# Sheet1.net
KiCad netlist of a schematic drawn in Altium Designer
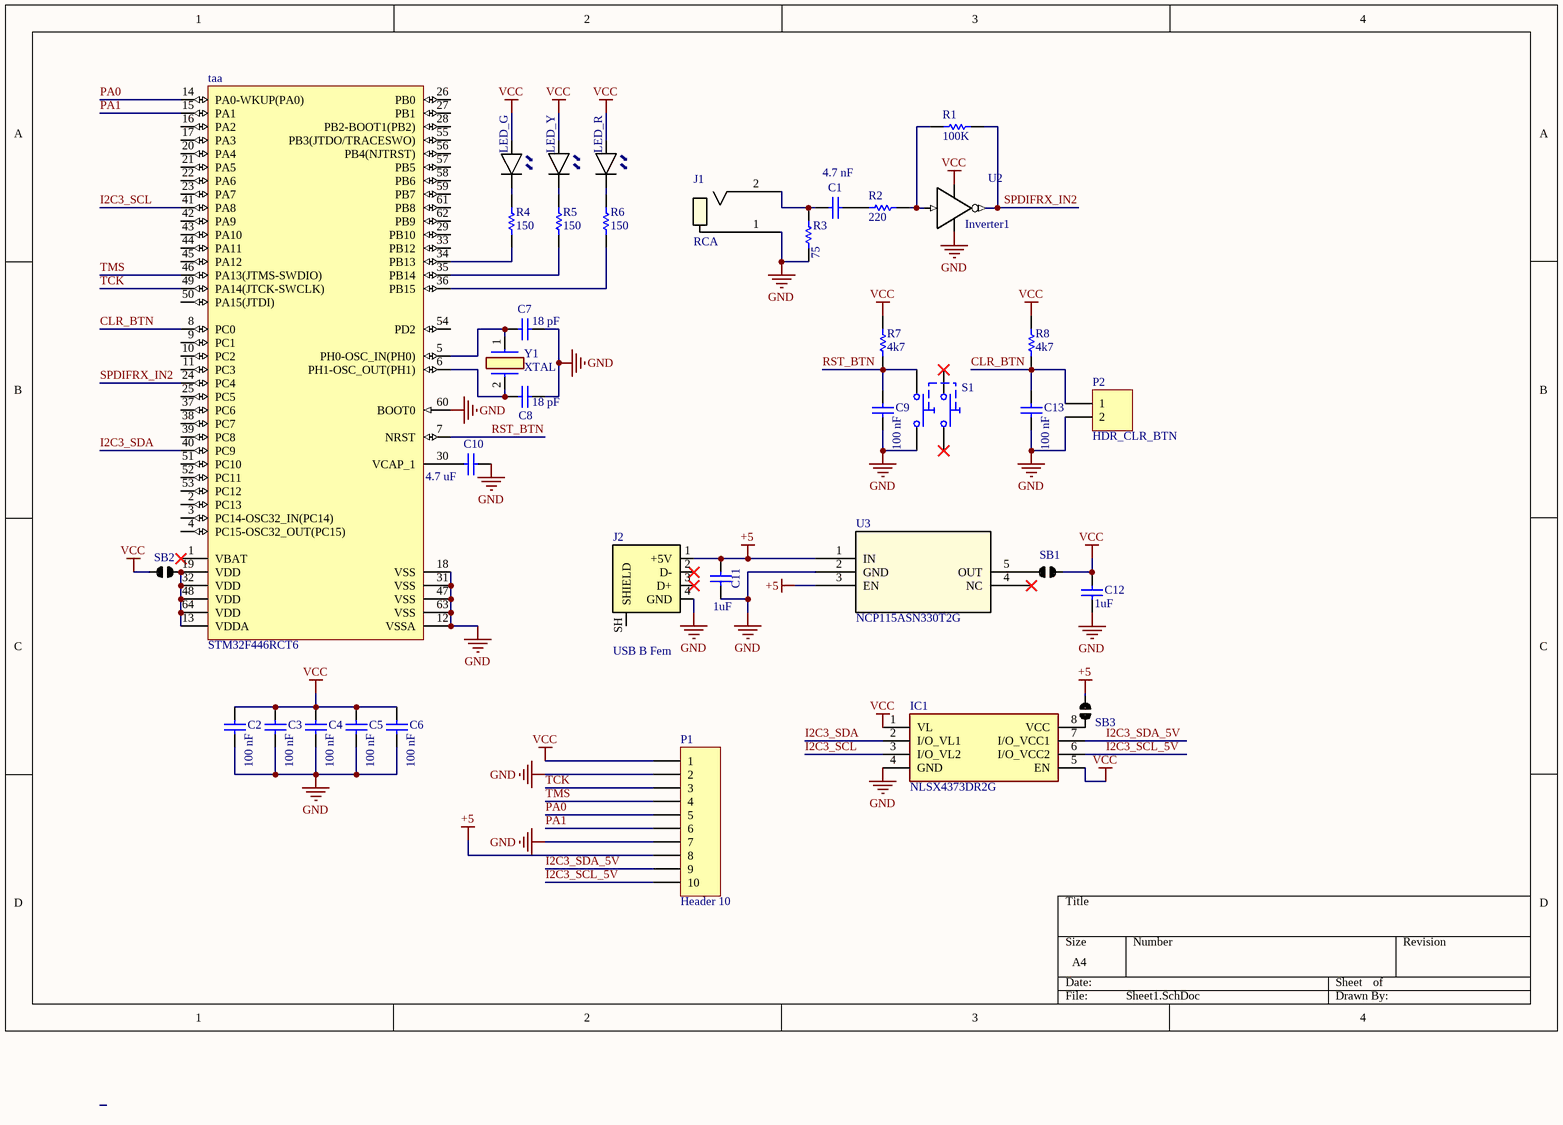
[diagram p0: Sheet1.SchDoc]

(export (version "E")
  (design (tool "Eeschema 10.0.6"))
  (components
    (comp (ref "C1")
      (value "4.7 nF")
      (footprint "RESC3216X70N")
      (description "Capacitor")
      (fields (field (name "Comment") "Cap") (field (name "PUBLISHER") "Altium Limited"))
      (libsource (lib "Miscellaneous Devices") (part "Cap"))
    )
    (comp (ref "C2")
      (value "100 nF")
      (footprint "RESC3216X70N")
      (description "Capacitor")
      (fields (field (name "Comment") "Cap") (field (name "PUBLISHER") "Altium Limited"))
      (libsource (lib "Miscellaneous Devices") (part "Cap"))
    )
    (comp (ref "C3")
      (value "100 nF")
      (footprint "RESC3216X70N")
      (description "Capacitor")
      (fields (field (name "Comment") "Cap") (field (name "PUBLISHER") "Altium Limited"))
      (libsource (lib "Miscellaneous Devices") (part "Cap"))
    )
    (comp (ref "C4")
      (value "100 nF")
      (footprint "RESC3216X70N")
      (description "Capacitor")
      (fields (field (name "Comment") "Cap") (field (name "PUBLISHER") "Altium Limited"))
      (libsource (lib "Miscellaneous Devices") (part "Cap"))
    )
    (comp (ref "C5")
      (value "100 nF")
      (footprint "RESC3216X70N")
      (description "Capacitor")
      (fields (field (name "Comment") "Cap") (field (name "PUBLISHER") "Altium Limited"))
      (libsource (lib "Miscellaneous Devices") (part "Cap"))
    )
    (comp (ref "C6")
      (value "100 nF")
      (footprint "RESC3216X70N")
      (description "Capacitor")
      (fields (field (name "Comment") "Cap") (field (name "PUBLISHER") "Altium Limited"))
      (libsource (lib "Miscellaneous Devices") (part "Cap"))
    )
    (comp (ref "C7")
      (value "18 pF")
      (footprint "RESC3216X70N")
      (description "Capacitor")
      (fields (field (name "Comment") "Cap") (field (name "PUBLISHER") "Altium Limited"))
      (libsource (lib "Miscellaneous Devices") (part "Cap"))
    )
    (comp (ref "C8")
      (value "18 pF")
      (footprint "RESC3216X70N")
      (description "Capacitor")
      (fields (field (name "Comment") "Cap") (field (name "PUBLISHER") "Altium Limited"))
      (libsource (lib "Miscellaneous Devices") (part "Cap"))
    )
    (comp (ref "C9")
      (value "100 nF")
      (footprint "RESC3216X70N")
      (description "Capacitor")
      (fields (field (name "Comment") "Cap") (field (name "PUBLISHER") "Altium Limited"))
      (libsource (lib "Miscellaneous Devices") (part "Cap"))
    )
    (comp (ref "C10")
      (value "4.7 uF")
      (footprint "CAPPRD250W50D655H1250")
      (description "Capacitor")
      (fields (field (name "Comment") "Cap") (field (name "PUBLISHER") "Altium Limited"))
      (libsource (lib "Miscellaneous Devices") (part "Cap"))
    )
    (comp (ref "C11")
      (value "1uF")
      (footprint "CAPPRD250W50D655H1250")
      (description "Capacitor")
      (fields (field (name "Comment") "Cap") (field (name "PUBLISHER") "Altium Limited"))
      (libsource (lib "Miscellaneous Devices") (part "Cap"))
    )
    (comp (ref "C12")
      (value "1uF")
      (footprint "CAPPRD250W50D655H1250")
      (description "Capacitor")
      (fields (field (name "Comment") "Cap") (field (name "PUBLISHER") "Altium Limited"))
      (libsource (lib "Miscellaneous Devices") (part "Cap"))
    )
    (comp (ref "C13")
      (value "100 nF")
      (footprint "RESC3216X70N")
      (description "Capacitor")
      (fields (field (name "Comment") "Cap") (field (name "PUBLISHER") "Altium Limited"))
      (libsource (lib "Miscellaneous Devices") (part "Cap"))
    )
    (comp (ref "IC1")
      (value "NLSX4373DR2G")
      (footprint "SamacSys:SOIC127P600X175-8N")
      (description "Integrated Circuit")
      (fields (field (name "MOUSER PART NUMBER") "863-NLSX4373DR2G"))
      (libsource (lib "*") (part "NLSX4373DR2G"))
    )
    (comp (ref "J1")
      (value "RCA")
      (footprint "KLPX-0848A-2-B_KYC")
      (description "No Description Available")
      (fields
        (field (name "MANUFACTURER_PART_NUMBER") "KLPX-0848A-2-B")
        (field (name "COPYRIGHT") "Copyright (C) 2023 Ultra Librarian. All rights reserved.")
      )
      (libsource (lib "KLPX-0848A-2-B") (part "KLPX-0848A-2-B"))
    )
    (comp (ref "J2") (value "USB B Fem") (footprint "UJ2BH1TH") (libsource (lib "USB") (part "USB B Fem")))
    (comp (ref "LED_G")
      (value "fucking led maat hoe moeilijk ist kutprogram")
      (footprint "LED_SSL-LX4673GD-LA20")
      (libsource (lib "Schlib1") (part "fucking led maat hoe moeilijk ist kutprogram"))
    )
    (comp (ref "LED_R")
      (value "fucking led maat hoe moeilijk ist kutprogram")
      (footprint "LED_SSL-LX4673GD-LA20")
      (libsource (lib "Schlib1") (part "fucking led maat hoe moeilijk ist kutprogram"))
    )
    (comp (ref "LED_Y")
      (value "fucking led maat hoe moeilijk ist kutprogram")
      (footprint "LED_SSL-LX4673GD-LA20")
      (libsource (lib "Schlib1") (part "fucking led maat hoe moeilijk ist kutprogram"))
    )
    (comp (ref "P1")
      (value "Header 10")
      (footprint "HDR1X10")
      (description "Header, 10-Pin")
      (fields (field (name "PUBLISHER") "Altium Limited"))
      (libsource (lib "Miscellaneous Connectors") (part "Header 10"))
    )
    (comp (ref "P2")
      (value "HDR_CLR_BTN")
      (footprint "HDR1X2")
      (description "Header, 2-Pin")
      (fields (field (name "PUBLISHER") "Altium Limited"))
      (libsource (lib "Miscellaneous Connectors") (part "Header 2"))
    )
    (comp (ref "R1")
      (value "100K")
      (footprint "RESC3216X70N")
      (description "Resistor")
      (fields (field (name "Comment") "Res1") (field (name "PUBLISHER") "Altium Limited"))
      (libsource (lib "Miscellaneous Devices") (part "Res1"))
    )
    (comp (ref "R2")
      (value "220")
      (footprint "RESC3216X70N")
      (description "Resistor")
      (fields (field (name "Comment") "Res1") (field (name "PUBLISHER") "Altium Limited"))
      (libsource (lib "Miscellaneous Devices") (part "Res1"))
    )
    (comp (ref "R3")
      (value "75")
      (footprint "RESC3216X70N")
      (description "Resistor")
      (fields (field (name "Comment") "Res1") (field (name "PUBLISHER") "Altium Limited"))
      (libsource (lib "Miscellaneous Devices") (part "Res1"))
    )
    (comp (ref "R4")
      (value "150")
      (footprint "RESC3216X70N")
      (description "Resistor")
      (fields (field (name "Comment") "Res1") (field (name "PUBLISHER") "Altium Limited"))
      (libsource (lib "Miscellaneous Devices") (part "Res1"))
    )
    (comp (ref "R5")
      (value "150")
      (footprint "RESC3216X70N")
      (description "Resistor")
      (fields (field (name "Comment") "Res1") (field (name "PUBLISHER") "Altium Limited"))
      (libsource (lib "Miscellaneous Devices") (part "Res1"))
    )
    (comp (ref "R6")
      (value "150")
      (footprint "RESC3216X70N")
      (description "Resistor")
      (fields (field (name "Comment") "Res1") (field (name "PUBLISHER") "Altium Limited"))
      (libsource (lib "Miscellaneous Devices") (part "Res1"))
    )
    (comp (ref "R7")
      (value "4k7")
      (footprint "RESC3216X70N")
      (description "Resistor")
      (fields (field (name "Comment") "Res1") (field (name "PUBLISHER") "Altium Limited"))
      (libsource (lib "Miscellaneous Devices") (part "Res1"))
    )
    (comp (ref "R8")
      (value "4k7")
      (footprint "RESC3216X70N")
      (description "Resistor")
      (fields (field (name "Comment") "Res1") (field (name "PUBLISHER") "Altium Limited"))
      (libsource (lib "Miscellaneous Devices") (part "Res1"))
    )
    (comp (ref "S1")
      (value "Doubl-Pole, Single-Throw Button")
      (footprint "TS026655BK160LCRD")
      (libsource (lib "Simulation Generic Components") (part "DPST Push Button"))
    )
    (comp (ref "SB1")
      (value "Solder Bridge")
      (footprint "Solder Bridge")
      (libsource (lib "schematic") (part "Solder Bridge"))
    )
    (comp (ref "SB2")
      (value "Solder Bridge")
      (footprint "Solder Bridge")
      (libsource (lib "schematic") (part "Solder Bridge"))
    )
    (comp (ref "SB3")
      (value "Solder Bridge")
      (footprint "Solder Bridge")
      (libsource (lib "") (part "Solder Bridge_1"))
    )
    (comp (ref "taa")
      (value "STM32F446RCT6")
      (footprint "STM-LQFP64_L")
      (libsource (lib "Altium Content Vault") (part "MC-ARM-STM32F446-LQFP64"))
    )
    (comp (ref "U2") (value "Inverter1") (footprint "DBV5-M") (libsource (lib "Schlib1") (part "Inverter1")))
    (comp (ref "U3")
      (value "NCP115ASN330T2G")
      (footprint "SOT95P275X120-5N")
      (description "No Description Available")
      (fields (field (name "COPYRIGHT") "Copyright (C) 2023 Ultra Librarian. All rights reserved."))
      (libsource (lib "NCP115ASN330T2G") (part "NCP115ASN330T2G"))
    )
    (comp (ref "Y1")
      (value "XTAL")
      (footprint "SamacSys:ECS80185PXGMTR")
      (description "Crystal or Oscillator")
      (fields
        (field (name "MANUFACTURER_PART_NUMBER") "ECS-80-18-5PX-GM-TR")
        (field (name "MOUSER PART NUMBER") "520-80-18-5PX-GM-TR")
      )
      (libsource (lib "Schlib1") (part "ECS-80-18-5PX-GM-TR"))
    )
  )
  (nets
    (net (code "1") (name "+5") (class "Default")
      (node (ref "C11") (pin "2") (pinfunction "2_2") (pintype "passive"))
      (node (ref "J2") (pin "1") (pinfunction "+5V_1") (pintype "power_in"))
      (node (ref "P1") (pin "8") (pinfunction "8_8") (pintype "passive"))
      (node (ref "SB3") (pin "2") (pinfunction "3_2") (pintype "passive"))
      (node (ref "U3") (pin "1") (pinfunction "IN_1") (pintype "passive"))
      (node (ref "U3") (pin "3") (pinfunction "EN_3") (pintype "passive"))
    )
    (net (code "2") (name "/CLR_BTN") (class "Default")
      (node (ref "C13") (pin "2") (pinfunction "2_2") (pintype "passive"))
      (node (ref "P2") (pin "1") (pinfunction "1_1") (pintype "passive"))
      (node (ref "R8") (pin "2") (pinfunction "2_2") (pintype "passive"))
      (node (ref "taa") (pin "8") (pinfunction "PC0_8") (pintype "bidirectional"))
    )
    (net (code "3") (name "/I2C3_SCL") (class "Default")
      (node (ref "IC1") (pin "3") (pinfunction "I/O_VL2_3") (pintype "passive"))
      (node (ref "taa") (pin "41") (pinfunction "PA8_41") (pintype "bidirectional"))
    )
    (net (code "4") (name "/I2C3_SCL_5V") (class "Default")
      (node (ref "IC1") (pin "6") (pinfunction "I/O_VCC2_6") (pintype "passive"))
      (node (ref "P1") (pin "10") (pinfunction "10_10") (pintype "passive"))
    )
    (net (code "5") (name "/I2C3_SDA") (class "Default")
      (node (ref "IC1") (pin "2") (pinfunction "I/O_VL1_2") (pintype "passive"))
      (node (ref "taa") (pin "40") (pinfunction "PC9_40") (pintype "bidirectional"))
    )
    (net (code "6") (name "/I2C3_SDA_5V") (class "Default")
      (node (ref "IC1") (pin "7") (pinfunction "I/O_VCC1_7") (pintype "passive"))
      (node (ref "P1") (pin "9") (pinfunction "9_9") (pintype "passive"))
    )
    (net (code "7") (name "/PA0") (class "Default")
      (node (ref "P1") (pin "5") (pinfunction "5_5") (pintype "passive"))
      (node (ref "taa") (pin "14") (pinfunction "PA0-WKUP(PA0)_14") (pintype "bidirectional"))
    )
    (net (code "8") (name "/PA1") (class "Default")
      (node (ref "P1") (pin "6") (pinfunction "6_6") (pintype "passive"))
      (node (ref "taa") (pin "15") (pinfunction "PA1_15") (pintype "bidirectional"))
    )
    (net (code "9") (name "/RST_BTN") (class "Default")
      (node (ref "C9") (pin "2") (pinfunction "2_2") (pintype "passive"))
      (node (ref "R7") (pin "2") (pinfunction "2_2") (pintype "passive"))
      (node (ref "S1") (pin "3") (pinfunction "3_3") (pintype "passive"))
      (node (ref "taa") (pin "7") (pinfunction "NRST_7") (pintype "bidirectional"))
    )
    (net (code "10") (name "/SPDIFRX_IN2") (class "Default")
      (node (ref "R1") (pin "1") (pinfunction "1_1") (pintype "passive"))
      (node (ref "U2") (pin "4") (pinfunction "Y_4") (pintype "output"))
      (node (ref "taa") (pin "24") (pinfunction "PC4_24") (pintype "bidirectional"))
    )
    (net (code "11") (name "/TCK") (class "Default")
      (node (ref "P1") (pin "3") (pinfunction "3_3") (pintype "passive"))
      (node (ref "taa") (pin "49") (pinfunction "PA14(JTCK-SWCLK)_49") (pintype "bidirectional"))
    )
    (net (code "12") (name "/TMS") (class "Default")
      (node (ref "P1") (pin "4") (pinfunction "4_4") (pintype "passive"))
      (node (ref "taa") (pin "46") (pinfunction "PA13(JTMS-SWDIO)_46") (pintype "bidirectional"))
    )
    (net (code "13") (name "GND") (class "Default")
      (node (ref "C10") (pin "2") (pinfunction "2_2") (pintype "passive"))
      (node (ref "C11") (pin "1") (pinfunction "1_1") (pintype "passive"))
      (node (ref "C12") (pin "1") (pinfunction "1_1") (pintype "passive"))
      (node (ref "C13") (pin "1") (pinfunction "1_1") (pintype "passive"))
      (node (ref "C2") (pin "1") (pinfunction "1_1") (pintype "passive"))
      (node (ref "C3") (pin "1") (pinfunction "1_1") (pintype "passive"))
      (node (ref "C4") (pin "1") (pinfunction "1_1") (pintype "passive"))
      (node (ref "C5") (pin "1") (pinfunction "1_1") (pintype "passive"))
      (node (ref "C6") (pin "1") (pinfunction "1_1") (pintype "passive"))
      (node (ref "C7") (pin "2") (pinfunction "2_2") (pintype "passive"))
      (node (ref "C8") (pin "2") (pinfunction "2_2") (pintype "passive"))
      (node (ref "C9") (pin "1") (pinfunction "1_1") (pintype "passive"))
      (node (ref "IC1") (pin "4") (pinfunction "GND_4") (pintype "passive"))
      (node (ref "J1") (pin "1") (pinfunction "1_1") (pintype "passive"))
      (node (ref "J2") (pin "4") (pinfunction "GND_4") (pintype "passive"))
      (node (ref "P1") (pin "2") (pinfunction "2_2") (pintype "passive"))
      (node (ref "P1") (pin "7") (pinfunction "7_7") (pintype "passive"))
      (node (ref "P2") (pin "2") (pinfunction "2_2") (pintype "passive"))
      (node (ref "R3") (pin "1") (pinfunction "1_1") (pintype "passive"))
      (node (ref "S1") (pin "4") (pinfunction "4_4") (pintype "passive"))
      (node (ref "U2") (pin "3") (pinfunction "GND_3") (pintype "passive"))
      (node (ref "U3") (pin "2") (pinfunction "GND_2") (pintype "power_in"))
      (node (ref "taa") (pin "12") (pinfunction "VSSA_12") (pintype "power_in"))
      (node (ref "taa") (pin "18") (pinfunction "VSS_18") (pintype "power_in"))
      (node (ref "taa") (pin "31") (pinfunction "VSS_31") (pintype "power_in"))
      (node (ref "taa") (pin "47") (pinfunction "VSS_47") (pintype "power_in"))
      (node (ref "taa") (pin "60") (pinfunction "BOOT0_60") (pintype "input"))
      (node (ref "taa") (pin "63") (pinfunction "VSS_63") (pintype "power_in"))
    )
    (net (code "14") (name "Net-(C1-Pad1)") (class "Default")
      (node (ref "C1") (pin "1") (pinfunction "1_1") (pintype "passive"))
      (node (ref "J1") (pin "2") (pinfunction "2_2") (pintype "passive"))
      (node (ref "R3") (pin "2") (pinfunction "2_2") (pintype "passive"))
    )
    (net (code "15") (name "Net-(C1-Pad2)") (class "Default")
      (node (ref "C1") (pin "2") (pinfunction "2_2") (pintype "passive"))
      (node (ref "R2") (pin "2") (pinfunction "2_2") (pintype "passive"))
    )
    (net (code "16") (name "Net-(IC1-VCC)") (class "Default")
      (node (ref "IC1") (pin "8") (pinfunction "VCC_8") (pintype "passive"))
      (node (ref "SB3") (pin "1") (pinfunction "3_1") (pintype "passive"))
    )
    (net (code "17") (name "Net-(LED_G-Pad2)") (class "Default")
      (node (ref "LED_G") (pin "2") (pinfunction "2_2") (pintype "passive"))
      (node (ref "R4") (pin "1") (pinfunction "1_1") (pintype "passive"))
    )
    (net (code "18") (name "Net-(LED_R-Pad2)") (class "Default")
      (node (ref "LED_R") (pin "2") (pinfunction "2_2") (pintype "passive"))
      (node (ref "R6") (pin "1") (pinfunction "1_1") (pintype "passive"))
    )
    (net (code "19") (name "Net-(LED_Y-Pad2)") (class "Default")
      (node (ref "LED_Y") (pin "2") (pinfunction "2_2") (pintype "passive"))
      (node (ref "R5") (pin "1") (pinfunction "1_1") (pintype "passive"))
    )
    (net (code "20") (name "Net-(U2-A)") (class "Default")
      (node (ref "R1") (pin "2") (pinfunction "2_2") (pintype "passive"))
      (node (ref "R2") (pin "1") (pinfunction "1_1") (pintype "passive"))
      (node (ref "U2") (pin "2") (pinfunction "A_2") (pintype "input"))
    )
    (net (code "21") (name "Net-(U3-OUT)") (class "Default")
      (node (ref "SB1") (pin "1") (pinfunction "3_1") (pintype "passive"))
      (node (ref "U3") (pin "5") (pinfunction "OUT_5") (pintype "passive"))
    )
    (net (code "22") (name "Net-(taa-PB13)") (class "Default")
      (node (ref "R4") (pin "2") (pinfunction "2_2") (pintype "passive"))
      (node (ref "taa") (pin "34") (pinfunction "PB13_34") (pintype "bidirectional"))
    )
    (net (code "23") (name "Net-(taa-PB14)") (class "Default")
      (node (ref "R5") (pin "2") (pinfunction "2_2") (pintype "passive"))
      (node (ref "taa") (pin "35") (pinfunction "PB14_35") (pintype "bidirectional"))
    )
    (net (code "24") (name "Net-(taa-PB15)") (class "Default")
      (node (ref "R6") (pin "2") (pinfunction "2_2") (pintype "passive"))
      (node (ref "taa") (pin "36") (pinfunction "PB15_36") (pintype "bidirectional"))
    )
    (net (code "25") (name "Net-(taa-PH0-OSC_IN(PH0))") (class "Default")
      (node (ref "C7") (pin "1") (pinfunction "1_1") (pintype "passive"))
      (node (ref "Y1") (pin "1") (pinfunction "1_1") (pintype "passive"))
      (node (ref "taa") (pin "5") (pinfunction "PH0-OSC_IN(PH0)_5") (pintype "bidirectional"))
    )
    (net (code "26") (name "Net-(taa-PH1-OSC_OUT(PH1))") (class "Default")
      (node (ref "C8") (pin "1") (pinfunction "1_1") (pintype "passive"))
      (node (ref "Y1") (pin "2") (pinfunction "2_2") (pintype "passive"))
      (node (ref "taa") (pin "6") (pinfunction "PH1-OSC_OUT(PH1)_6") (pintype "bidirectional"))
    )
    (net (code "27") (name "Net-(taa-VCAP_1)") (class "Default")
      (node (ref "C10") (pin "1") (pinfunction "1_1") (pintype "passive"))
      (node (ref "taa") (pin "30") (pinfunction "VCAP_1_30") (pintype "passive"))
    )
    (net (code "28") (name "Net-(taa-VDDA)") (class "Default")
      (node (ref "SB2") (pin "2") (pinfunction "3_2") (pintype "passive"))
      (node (ref "taa") (pin "13") (pinfunction "VDDA_13") (pintype "power_in"))
      (node (ref "taa") (pin "19") (pinfunction "VDD_19") (pintype "power_in"))
      (node (ref "taa") (pin "32") (pinfunction "VDD_32") (pintype "power_in"))
      (node (ref "taa") (pin "48") (pinfunction "VDD_48") (pintype "power_in"))
      (node (ref "taa") (pin "64") (pinfunction "VDD_64") (pintype "power_in"))
    )
    (net (code "29") (name "VCC") (class "Default")
      (node (ref "C12") (pin "2") (pinfunction "2_2") (pintype "passive"))
      (node (ref "C2") (pin "2") (pinfunction "2_2") (pintype "passive"))
      (node (ref "C3") (pin "2") (pinfunction "2_2") (pintype "passive"))
      (node (ref "C4") (pin "2") (pinfunction "2_2") (pintype "passive"))
      (node (ref "C5") (pin "2") (pinfunction "2_2") (pintype "passive"))
      (node (ref "C6") (pin "2") (pinfunction "2_2") (pintype "passive"))
      (node (ref "IC1") (pin "1") (pinfunction "VL_1") (pintype "passive"))
      (node (ref "IC1") (pin "5") (pinfunction "EN_5") (pintype "passive"))
      (node (ref "LED_G") (pin "1") (pinfunction "1_1") (pintype "passive"))
      (node (ref "LED_R") (pin "1") (pinfunction "1_1") (pintype "passive"))
      (node (ref "LED_Y") (pin "1") (pinfunction "1_1") (pintype "passive"))
      (node (ref "P1") (pin "1") (pinfunction "1_1") (pintype "passive"))
      (node (ref "R7") (pin "1") (pinfunction "1_1") (pintype "passive"))
      (node (ref "R8") (pin "1") (pinfunction "1_1") (pintype "passive"))
      (node (ref "SB1") (pin "2") (pinfunction "3_2") (pintype "passive"))
      (node (ref "SB2") (pin "1") (pinfunction "3_1") (pintype "passive"))
      (node (ref "U2") (pin "5") (pinfunction "VCC_5") (pintype "passive"))
    )
    (net (code "30") (name "unconnected-(J2-D+-Pad3)") (class "Default")
      (node (ref "J2") (pin "3") (pinfunction "D+_3") (pintype "bidirectional+no_connect"))
    )
    (net (code "31") (name "unconnected-(J2-D--Pad2)") (class "Default")
      (node (ref "J2") (pin "2") (pinfunction "D-_2") (pintype "bidirectional+no_connect"))
    )
    (net (code "32") (name "unconnected-(J2-SHIELD-PadSH)") (class "Default")
      (node (ref "J2") (pin "SH") (pinfunction "SHIELD_SH") (pintype "passive"))
    )
    (net (code "33") (name "unconnected-(S1-Pad1)") (class "Default")
      (node (ref "S1") (pin "1") (pinfunction "1_1") (pintype "passive+no_connect"))
    )
    (net (code "34") (name "unconnected-(S1-Pad2)") (class "Default")
      (node (ref "S1") (pin "2") (pinfunction "2_2") (pintype "passive+no_connect"))
    )
    (net (code "35") (name "unconnected-(U3-NC-Pad4)") (class "Default")
      (node (ref "U3") (pin "4") (pinfunction "NC_4") (pintype "passive+no_connect"))
    )
    (net (code "36") (name "unconnected-(taa-PA2-Pad16)") (class "Default")
      (node (ref "taa") (pin "16") (pinfunction "PA2_16") (pintype "bidirectional"))
    )
    (net (code "37") (name "unconnected-(taa-PA3-Pad17)") (class "Default")
      (node (ref "taa") (pin "17") (pinfunction "PA3_17") (pintype "bidirectional"))
    )
    (net (code "38") (name "unconnected-(taa-PA4-Pad20)") (class "Default")
      (node (ref "taa") (pin "20") (pinfunction "PA4_20") (pintype "bidirectional"))
    )
    (net (code "39") (name "unconnected-(taa-PA5-Pad21)") (class "Default")
      (node (ref "taa") (pin "21") (pinfunction "PA5_21") (pintype "bidirectional"))
    )
    (net (code "40") (name "unconnected-(taa-PA6-Pad22)") (class "Default")
      (node (ref "taa") (pin "22") (pinfunction "PA6_22") (pintype "bidirectional"))
    )
    (net (code "41") (name "unconnected-(taa-PA7-Pad23)") (class "Default")
      (node (ref "taa") (pin "23") (pinfunction "PA7_23") (pintype "bidirectional"))
    )
    (net (code "42") (name "unconnected-(taa-PA9-Pad42)") (class "Default")
      (node (ref "taa") (pin "42") (pinfunction "PA9_42") (pintype "bidirectional"))
    )
    (net (code "43") (name "unconnected-(taa-PA10-Pad43)") (class "Default")
      (node (ref "taa") (pin "43") (pinfunction "PA10_43") (pintype "bidirectional"))
    )
    (net (code "44") (name "unconnected-(taa-PA11-Pad44)") (class "Default")
      (node (ref "taa") (pin "44") (pinfunction "PA11_44") (pintype "bidirectional"))
    )
    (net (code "45") (name "unconnected-(taa-PA12-Pad45)") (class "Default")
      (node (ref "taa") (pin "45") (pinfunction "PA12_45") (pintype "bidirectional"))
    )
    (net (code "46") (name "unconnected-(taa-PA15(JTDI)-Pad50)") (class "Default")
      (node (ref "taa") (pin "50") (pinfunction "PA15(JTDI)_50") (pintype "bidirectional"))
    )
    (net (code "47") (name "unconnected-(taa-PB0-Pad26)") (class "Default")
      (node (ref "taa") (pin "26") (pinfunction "PB0_26") (pintype "bidirectional"))
    )
    (net (code "48") (name "unconnected-(taa-PB1-Pad27)") (class "Default")
      (node (ref "taa") (pin "27") (pinfunction "PB1_27") (pintype "bidirectional"))
    )
    (net (code "49") (name "unconnected-(taa-PB2-BOOT1(PB2)-Pad28)") (class "Default")
      (node (ref "taa") (pin "28") (pinfunction "PB2-BOOT1(PB2)_28") (pintype "bidirectional"))
    )
    (net (code "50") (name "unconnected-(taa-PB3(JTDO{slash}TRACESWO)-Pad55)") (class "Default")
      (node (ref "taa") (pin "55") (pinfunction "PB3(JTDO/TRACESWO)_55") (pintype "bidirectional"))
    )
    (net (code "51") (name "unconnected-(taa-PB4(NJTRST)-Pad56)") (class "Default")
      (node (ref "taa") (pin "56") (pinfunction "PB4(NJTRST)_56") (pintype "bidirectional"))
    )
    (net (code "52") (name "unconnected-(taa-PB5-Pad57)") (class "Default")
      (node (ref "taa") (pin "57") (pinfunction "PB5_57") (pintype "bidirectional"))
    )
    (net (code "53") (name "unconnected-(taa-PB6-Pad58)") (class "Default")
      (node (ref "taa") (pin "58") (pinfunction "PB6_58") (pintype "bidirectional"))
    )
    (net (code "54") (name "unconnected-(taa-PB7-Pad59)") (class "Default")
      (node (ref "taa") (pin "59") (pinfunction "PB7_59") (pintype "bidirectional"))
    )
    (net (code "55") (name "unconnected-(taa-PB8-Pad61)") (class "Default")
      (node (ref "taa") (pin "61") (pinfunction "PB8_61") (pintype "bidirectional"))
    )
    (net (code "56") (name "unconnected-(taa-PB9-Pad62)") (class "Default")
      (node (ref "taa") (pin "62") (pinfunction "PB9_62") (pintype "bidirectional"))
    )
    (net (code "57") (name "unconnected-(taa-PB10-Pad29)") (class "Default")
      (node (ref "taa") (pin "29") (pinfunction "PB10_29") (pintype "bidirectional"))
    )
    (net (code "58") (name "unconnected-(taa-PB12-Pad33)") (class "Default")
      (node (ref "taa") (pin "33") (pinfunction "PB12_33") (pintype "bidirectional"))
    )
    (net (code "59") (name "unconnected-(taa-PC1-Pad9)") (class "Default")
      (node (ref "taa") (pin "9") (pinfunction "PC1_9") (pintype "bidirectional"))
    )
    (net (code "60") (name "unconnected-(taa-PC2-Pad10)") (class "Default")
      (node (ref "taa") (pin "10") (pinfunction "PC2_10") (pintype "bidirectional"))
    )
    (net (code "61") (name "unconnected-(taa-PC3-Pad11)") (class "Default")
      (node (ref "taa") (pin "11") (pinfunction "PC3_11") (pintype "bidirectional"))
    )
    (net (code "62") (name "unconnected-(taa-PC5-Pad25)") (class "Default")
      (node (ref "taa") (pin "25") (pinfunction "PC5_25") (pintype "bidirectional"))
    )
    (net (code "63") (name "unconnected-(taa-PC6-Pad37)") (class "Default")
      (node (ref "taa") (pin "37") (pinfunction "PC6_37") (pintype "bidirectional"))
    )
    (net (code "64") (name "unconnected-(taa-PC7-Pad38)") (class "Default")
      (node (ref "taa") (pin "38") (pinfunction "PC7_38") (pintype "bidirectional"))
    )
    (net (code "65") (name "unconnected-(taa-PC8-Pad39)") (class "Default")
      (node (ref "taa") (pin "39") (pinfunction "PC8_39") (pintype "bidirectional"))
    )
    (net (code "66") (name "unconnected-(taa-PC10-Pad51)") (class "Default")
      (node (ref "taa") (pin "51") (pinfunction "PC10_51") (pintype "bidirectional"))
    )
    (net (code "67") (name "unconnected-(taa-PC11-Pad52)") (class "Default")
      (node (ref "taa") (pin "52") (pinfunction "PC11_52") (pintype "bidirectional"))
    )
    (net (code "68") (name "unconnected-(taa-PC12-Pad53)") (class "Default")
      (node (ref "taa") (pin "53") (pinfunction "PC12_53") (pintype "bidirectional"))
    )
    (net (code "69") (name "unconnected-(taa-PC13-Pad2)") (class "Default")
      (node (ref "taa") (pin "2") (pinfunction "PC13_2") (pintype "bidirectional"))
    )
    (net (code "70") (name "unconnected-(taa-PC14-OSC32_IN(PC14)-Pad3)") (class "Default")
      (node (ref "taa") (pin "3") (pinfunction "PC14-OSC32_IN(PC14)_3") (pintype "bidirectional"))
    )
    (net (code "71") (name "unconnected-(taa-PC15-OSC32_OUT(PC15)-Pad4)") (class "Default")
      (node (ref "taa") (pin "4") (pinfunction "PC15-OSC32_OUT(PC15)_4") (pintype "bidirectional"))
    )
    (net (code "72") (name "unconnected-(taa-PD2-Pad54)") (class "Default")
      (node (ref "taa") (pin "54") (pinfunction "PD2_54") (pintype "bidirectional"))
    )
    (net (code "73") (name "unconnected-(taa-VBAT-Pad1)") (class "Default")
      (node (ref "taa") (pin "1") (pinfunction "VBAT_1") (pintype "power_in+no_connect"))
    )
  )
)
